# BK5811.net
KiCad netlist of a schematic drawn in Altium Designer
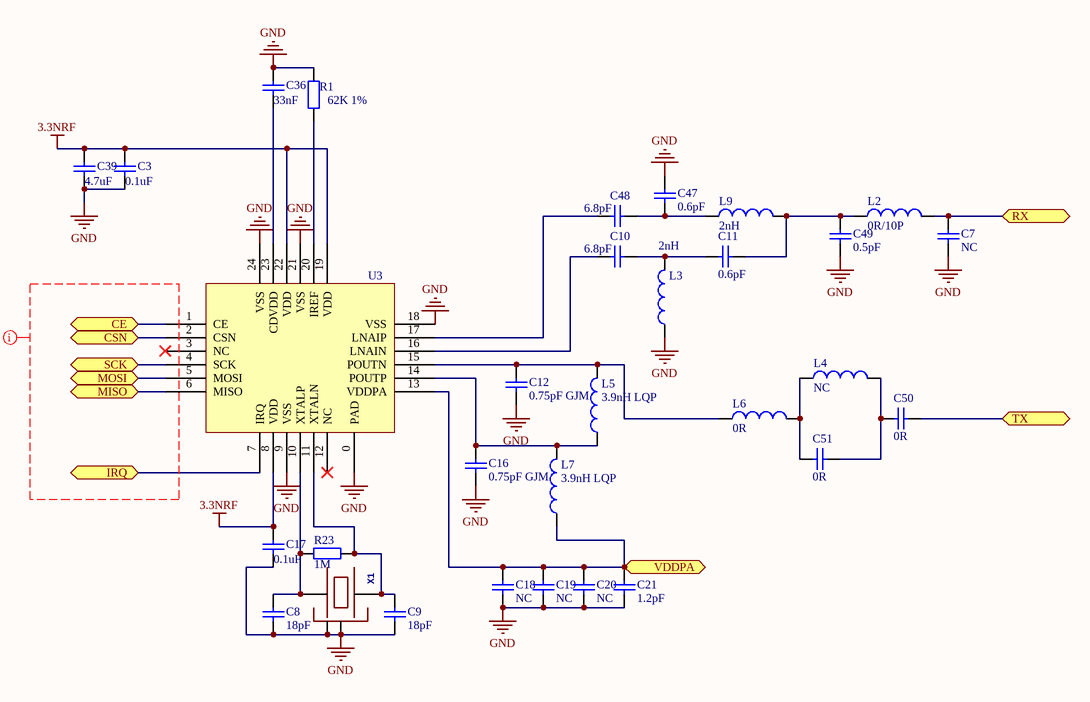
[diagram p0: BK5811.SchDoc]

(export (version "E")
  (design (tool "Eeschema 10.0.6"))
  (components
    (comp (ref "C3")
      (value "0.1uF")
      (footprint "0402")
      (description "Capacitor")
      (fields (field (name "PUBLISHER") "Altium Limited"))
      (libsource (lib "RTC6705") (part "Cap"))
    )
    (comp (ref "C7")
      (value "NC")
      (footprint "0402")
      (description "Capacitor")
      (fields (field (name "PUBLISHER") "Altium Limited"))
      (libsource (lib "RTC6705") (part "Cap"))
    )
    (comp (ref "C8")
      (value "18pF")
      (footprint "0402")
      (description "Capacitor")
      (fields (field (name "Comment") "Cap") (field (name "PUBLISHER") "Altium Limited"))
      (libsource (lib "RTC6705") (part "Cap"))
    )
    (comp (ref "C9")
      (value "18pF")
      (footprint "0402")
      (description "Capacitor")
      (fields (field (name "Comment") "Cap") (field (name "PUBLISHER") "Altium Limited"))
      (libsource (lib "RTC6705") (part "Cap"))
    )
    (comp (ref "C10")
      (value "6.8pF")
      (footprint "0402")
      (description "Capacitor")
      (fields (field (name "PUBLISHER") "Altium Limited"))
      (libsource (lib "RTC6705") (part "Cap"))
    )
    (comp (ref "C11")
      (value "0.6pF")
      (footprint "0402")
      (description "Capacitor")
      (fields (field (name "PUBLISHER") "Altium Limited"))
      (libsource (lib "RTC6705") (part "Cap"))
    )
    (comp (ref "C12")
      (value "0.75pF GJM")
      (footprint "0402")
      (description "Capacitor")
      (fields (field (name "PUBLISHER") "Altium Limited"))
      (libsource (lib "RTC6705") (part "Cap"))
    )
    (comp (ref "C16")
      (value "0.75pF GJM")
      (footprint "0402")
      (description "Capacitor")
      (fields (field (name "PUBLISHER") "Altium Limited"))
      (libsource (lib "RTC6705") (part "Cap"))
    )
    (comp (ref "C17")
      (value "0.1uF")
      (footprint "0402")
      (description "Capacitor")
      (fields (field (name "PUBLISHER") "Altium Limited"))
      (libsource (lib "RTC6705") (part "Cap"))
    )
    (comp (ref "C18")
      (value "NC")
      (footprint "0402")
      (description "Capacitor")
      (fields (field (name "PUBLISHER") "Altium Limited"))
      (libsource (lib "RTC6705") (part "Cap"))
    )
    (comp (ref "C19")
      (value "NC")
      (footprint "0402")
      (description "Capacitor")
      (fields (field (name "PUBLISHER") "Altium Limited"))
      (libsource (lib "RTC6705") (part "Cap"))
    )
    (comp (ref "C20")
      (value "NC")
      (footprint "0402")
      (description "Capacitor")
      (fields (field (name "PUBLISHER") "Altium Limited"))
      (libsource (lib "RTC6705") (part "Cap"))
    )
    (comp (ref "C21")
      (value "1.2pF")
      (footprint "0402")
      (description "Capacitor")
      (fields (field (name "PUBLISHER") "Altium Limited"))
      (libsource (lib "RTC6705") (part "Cap"))
    )
    (comp (ref "C36")
      (value "33nF")
      (footprint "0402")
      (description "Capacitor")
      (fields (field (name "PUBLISHER") "Altium Limited"))
      (libsource (lib "RTC6705") (part "Cap"))
    )
    (comp (ref "C39")
      (value "4.7uF")
      (footprint "0603")
      (description "Capacitor")
      (fields (field (name "PUBLISHER") "Altium Limited"))
      (libsource (lib "RTC6705") (part "Cap"))
    )
    (comp (ref "C47")
      (value "0.6pF")
      (footprint "0402")
      (description "Capacitor")
      (fields (field (name "PUBLISHER") "Altium Limited"))
      (libsource (lib "RTC6705") (part "Cap"))
    )
    (comp (ref "C48")
      (value "6.8pF")
      (footprint "0402")
      (description "Capacitor")
      (fields (field (name "PUBLISHER") "Altium Limited"))
      (libsource (lib "RTC6705") (part "Cap"))
    )
    (comp (ref "C49")
      (value "0.5pF")
      (footprint "0402")
      (description "Capacitor")
      (fields (field (name "PUBLISHER") "Altium Limited"))
      (libsource (lib "RTC6705") (part "Cap"))
    )
    (comp (ref "C50")
      (value "0R")
      (footprint "0402")
      (description "Capacitor")
      (fields (field (name "PUBLISHER") "Altium Limited"))
      (libsource (lib "RTC6705") (part "Cap"))
    )
    (comp (ref "C51")
      (value "0R")
      (footprint "0402")
      (description "Capacitor")
      (fields (field (name "PUBLISHER") "Altium Limited"))
      (libsource (lib "RTC6705") (part "Cap"))
    )
    (comp (ref "L2")
      (value "0R/10P")
      (footprint "0402")
      (description "Inductor")
      (fields (field (name "PUBLISHER") "Altium Limited"))
      (libsource (lib "Miscellaneous Devices") (part "Inductor"))
    )
    (comp (ref "L3")
      (value "2nH")
      (footprint "0402")
      (description "Inductor")
      (fields (field (name "PUBLISHER") "Altium Limited"))
      (libsource (lib "Miscellaneous Devices") (part "Inductor"))
    )
    (comp (ref "L4")
      (value "NC")
      (footprint "0402")
      (description "Inductor")
      (fields (field (name "PUBLISHER") "Altium Limited"))
      (libsource (lib "Miscellaneous Devices") (part "Inductor"))
    )
    (comp (ref "L5")
      (value "3.9nH LQP")
      (footprint "0402")
      (description "Inductor")
      (fields (field (name "PUBLISHER") "Altium Limited"))
      (libsource (lib "Miscellaneous Devices") (part "Inductor"))
    )
    (comp (ref "L6")
      (value "0R")
      (footprint "0402")
      (description "Inductor")
      (fields (field (name "PUBLISHER") "Altium Limited"))
      (libsource (lib "Miscellaneous Devices") (part "Inductor"))
    )
    (comp (ref "L7")
      (value "3.9nH LQP")
      (footprint "0402")
      (description "Inductor")
      (fields (field (name "PUBLISHER") "Altium Limited"))
      (libsource (lib "Miscellaneous Devices") (part "Inductor"))
    )
    (comp (ref "L9")
      (value "2nH")
      (footprint "0402")
      (description "Inductor")
      (fields (field (name "PUBLISHER") "Altium Limited"))
      (libsource (lib "Miscellaneous Devices") (part "Inductor"))
    )
    (comp (ref "R1")
      (value "62K 1%")
      (footprint "0402")
      (description "Resistor")
      (fields (field (name "PUBLISHER") "Altium Limited"))
      (libsource (lib "RTC6705") (part "Res2"))
    )
    (comp (ref "R23")
      (value "1M")
      (footprint "0402")
      (description "Resistor")
      (fields (field (name "Comment") "Res2") (field (name "PUBLISHER") "Altium Limited"))
      (libsource (lib "") (part "Res2_1"))
    )
    (comp (ref "U3") (value "BK5811") (footprint "BK5811") (libsource (lib "BK5811") (part "BK5811")))
    (comp (ref "X1")
      (value "16Mhz")
      (footprint "OSCILLATOR-3.2X2.5")
      (description "Crystal Oscillator in 3.2x2.5 SMD")
      (libsource (lib "pixhawk2") (part "OSCILLATOR-3.2X2.5"))
    )
  )
  (nets
    (net (code "1") (name "/CE") (class "Default")
      (node (ref "U3") (pin "1") (pinfunction "CE_1") (pintype "passive"))
    )
    (net (code "2") (name "/CSN") (class "Default")
      (node (ref "U3") (pin "2") (pinfunction "CSN_2") (pintype "passive"))
    )
    (net (code "3") (name "/IRQ") (class "Default")
      (node (ref "U3") (pin "7") (pinfunction "IRQ_7") (pintype "passive"))
    )
    (net (code "4") (name "/MISO") (class "Default")
      (node (ref "U3") (pin "6") (pinfunction "MISO_6") (pintype "passive"))
    )
    (net (code "5") (name "/MOSI") (class "Default")
      (node (ref "U3") (pin "5") (pinfunction "MOSI_5") (pintype "passive"))
    )
    (net (code "6") (name "/RX") (class "Default")
      (node (ref "C7") (pin "2") (pinfunction "2_2") (pintype "passive"))
      (node (ref "L2") (pin "2") (pinfunction "2_2") (pintype "passive"))
    )
    (net (code "7") (name "/SCK") (class "Default")
      (node (ref "U3") (pin "4") (pinfunction "SCK_4") (pintype "passive"))
    )
    (net (code "8") (name "/TX") (class "Default")
      (node (ref "C50") (pin "2") (pinfunction "2_2") (pintype "passive"))
    )
    (net (code "9") (name "/VDDPA") (class "Default")
      (node (ref "C18") (pin "1") (pinfunction "1_1") (pintype "passive"))
      (node (ref "C19") (pin "1") (pinfunction "1_1") (pintype "passive"))
      (node (ref "C20") (pin "1") (pinfunction "1_1") (pintype "passive"))
      (node (ref "C21") (pin "1") (pinfunction "1_1") (pintype "passive"))
      (node (ref "L7") (pin "1") (pinfunction "1_1") (pintype "passive"))
      (node (ref "U3") (pin "13") (pinfunction "VDDPA_13") (pintype "passive"))
    )
    (net (code "10") (name "3.3NRF") (class "Default")
      (node (ref "C17") (pin "2") (pinfunction "2_2") (pintype "passive"))
      (node (ref "C3") (pin "2") (pinfunction "2_2") (pintype "passive"))
      (node (ref "C39") (pin "2") (pinfunction "2_2") (pintype "passive"))
      (node (ref "U3") (pin "19") (pinfunction "VDD_19") (pintype "passive"))
      (node (ref "U3") (pin "22") (pinfunction "VDD_22") (pintype "passive"))
      (node (ref "U3") (pin "8") (pinfunction "VDD_8") (pintype "passive"))
    )
    (net (code "11") (name "GND") (class "Default")
      (node (ref "C12") (pin "1") (pinfunction "1_1") (pintype "passive"))
      (node (ref "C16") (pin "1") (pinfunction "1_1") (pintype "passive"))
      (node (ref "C17") (pin "1") (pinfunction "1_1") (pintype "passive"))
      (node (ref "C18") (pin "2") (pinfunction "2_2") (pintype "passive"))
      (node (ref "C19") (pin "2") (pinfunction "2_2") (pintype "passive"))
      (node (ref "C20") (pin "2") (pinfunction "2_2") (pintype "passive"))
      (node (ref "C21") (pin "2") (pinfunction "2_2") (pintype "passive"))
      (node (ref "C3") (pin "1") (pinfunction "1_1") (pintype "passive"))
      (node (ref "C36") (pin "2") (pinfunction "2_2") (pintype "passive"))
      (node (ref "C39") (pin "1") (pinfunction "1_1") (pintype "passive"))
      (node (ref "C47") (pin "2") (pinfunction "2_2") (pintype "passive"))
      (node (ref "C49") (pin "1") (pinfunction "1_1") (pintype "passive"))
      (node (ref "C7") (pin "1") (pinfunction "1_1") (pintype "passive"))
      (node (ref "C8") (pin "2") (pinfunction "2_2") (pintype "passive"))
      (node (ref "C9") (pin "2") (pinfunction "2_2") (pintype "passive"))
      (node (ref "L3") (pin "1") (pinfunction "1_1") (pintype "passive"))
      (node (ref "R1") (pin "2") (pinfunction "2_2") (pintype "passive"))
      (node (ref "U3") (pin "0") (pinfunction "PAD_0") (pintype "passive"))
      (node (ref "U3") (pin "18") (pinfunction "VSS_18") (pintype "passive"))
      (node (ref "U3") (pin "21") (pinfunction "VSS_21") (pintype "passive"))
      (node (ref "U3") (pin "24") (pinfunction "VSS_24") (pintype "passive"))
      (node (ref "U3") (pin "9") (pinfunction "VSS_9") (pintype "passive"))
      (node (ref "X1") (pin "2") (pinfunction "NC_2_2") (pintype "open_emitter"))
      (node (ref "X1") (pin "4") (pinfunction "NC_4_4") (pintype "open_emitter"))
    )
    (net (code "12") (name "Net-(C10-Pad2)") (class "Default")
      (node (ref "C10") (pin "2") (pinfunction "2_2") (pintype "passive"))
      (node (ref "C11") (pin "2") (pinfunction "2_2") (pintype "passive"))
      (node (ref "L3") (pin "2") (pinfunction "2_2") (pintype "passive"))
    )
    (net (code "13") (name "Net-(C11-Pad1)") (class "Default")
      (node (ref "C11") (pin "1") (pinfunction "1_1") (pintype "passive"))
      (node (ref "C49") (pin "2") (pinfunction "2_2") (pintype "passive"))
      (node (ref "L2") (pin "1") (pinfunction "1_1") (pintype "passive"))
      (node (ref "L9") (pin "2") (pinfunction "2_2") (pintype "passive"))
    )
    (net (code "14") (name "Net-(C47-Pad1)") (class "Default")
      (node (ref "C47") (pin "1") (pinfunction "1_1") (pintype "passive"))
      (node (ref "C48") (pin "2") (pinfunction "2_2") (pintype "passive"))
      (node (ref "L9") (pin "1") (pinfunction "1_1") (pintype "passive"))
    )
    (net (code "15") (name "Net-(C50-Pad1)") (class "Default")
      (node (ref "C50") (pin "1") (pinfunction "1_1") (pintype "passive"))
      (node (ref "C51") (pin "2") (pinfunction "2_2") (pintype "passive"))
      (node (ref "L4") (pin "2") (pinfunction "2_2") (pintype "passive"))
    )
    (net (code "16") (name "Net-(C51-Pad1)") (class "Default")
      (node (ref "C51") (pin "1") (pinfunction "1_1") (pintype "passive"))
      (node (ref "L4") (pin "1") (pinfunction "1_1") (pintype "passive"))
      (node (ref "L6") (pin "2") (pinfunction "2_2") (pintype "passive"))
    )
    (net (code "17") (name "Net-(U3-CDVDD)") (class "Default")
      (node (ref "C36") (pin "1") (pinfunction "1_1") (pintype "passive"))
      (node (ref "U3") (pin "23") (pinfunction "CDVDD_23") (pintype "passive"))
    )
    (net (code "18") (name "Net-(U3-IREF)") (class "Default")
      (node (ref "R1") (pin "1") (pinfunction "1_1") (pintype "passive"))
      (node (ref "U3") (pin "20") (pinfunction "IREF_20") (pintype "passive"))
    )
    (net (code "19") (name "Net-(U3-LNAIN)") (class "Default")
      (node (ref "C10") (pin "1") (pinfunction "1_1") (pintype "passive"))
      (node (ref "U3") (pin "16") (pinfunction "LNAIN_16") (pintype "passive"))
    )
    (net (code "20") (name "Net-(U3-LNAIP)") (class "Default")
      (node (ref "C48") (pin "1") (pinfunction "1_1") (pintype "passive"))
      (node (ref "U3") (pin "17") (pinfunction "LNAIP_17") (pintype "passive"))
    )
    (net (code "21") (name "Net-(U3-POUTN)") (class "Default")
      (node (ref "C12") (pin "2") (pinfunction "2_2") (pintype "passive"))
      (node (ref "L5") (pin "2") (pinfunction "2_2") (pintype "passive"))
      (node (ref "L6") (pin "1") (pinfunction "1_1") (pintype "passive"))
      (node (ref "U3") (pin "15") (pinfunction "POUTN_15") (pintype "passive"))
    )
    (net (code "22") (name "Net-(U3-POUTP)") (class "Default")
      (node (ref "C16") (pin "2") (pinfunction "2_2") (pintype "passive"))
      (node (ref "L5") (pin "1") (pinfunction "1_1") (pintype "passive"))
      (node (ref "L7") (pin "2") (pinfunction "2_2") (pintype "passive"))
      (node (ref "U3") (pin "14") (pinfunction "POUTP_14") (pintype "passive"))
    )
    (net (code "23") (name "Net-(U3-XTALN)") (class "Default")
      (node (ref "C9") (pin "1") (pinfunction "1_1") (pintype "passive"))
      (node (ref "R23") (pin "1") (pinfunction "1_1") (pintype "passive"))
      (node (ref "U3") (pin "11") (pinfunction "XTALN_11") (pintype "passive"))
      (node (ref "X1") (pin "3") (pinfunction "3_3") (pintype "passive"))
    )
    (net (code "24") (name "Net-(U3-XTALP)") (class "Default")
      (node (ref "C8") (pin "1") (pinfunction "1_1") (pintype "passive"))
      (node (ref "R23") (pin "2") (pinfunction "2_2") (pintype "passive"))
      (node (ref "U3") (pin "10") (pinfunction "XTALP_10") (pintype "passive"))
      (node (ref "X1") (pin "1") (pinfunction "1_1") (pintype "passive"))
    )
    (net (code "25") (name "unconnected-(U3-NC-Pad3)") (class "Default")
      (node (ref "U3") (pin "3") (pinfunction "NC_3") (pintype "passive+no_connect"))
    )
    (net (code "26") (name "unconnected-(U3-NC-Pad12)") (class "Default")
      (node (ref "U3") (pin "12") (pinfunction "NC_12") (pintype "passive+no_connect"))
    )
  )
)
